# esquematico.net
KiCad netlist of a schematic drawn in Altium Designer
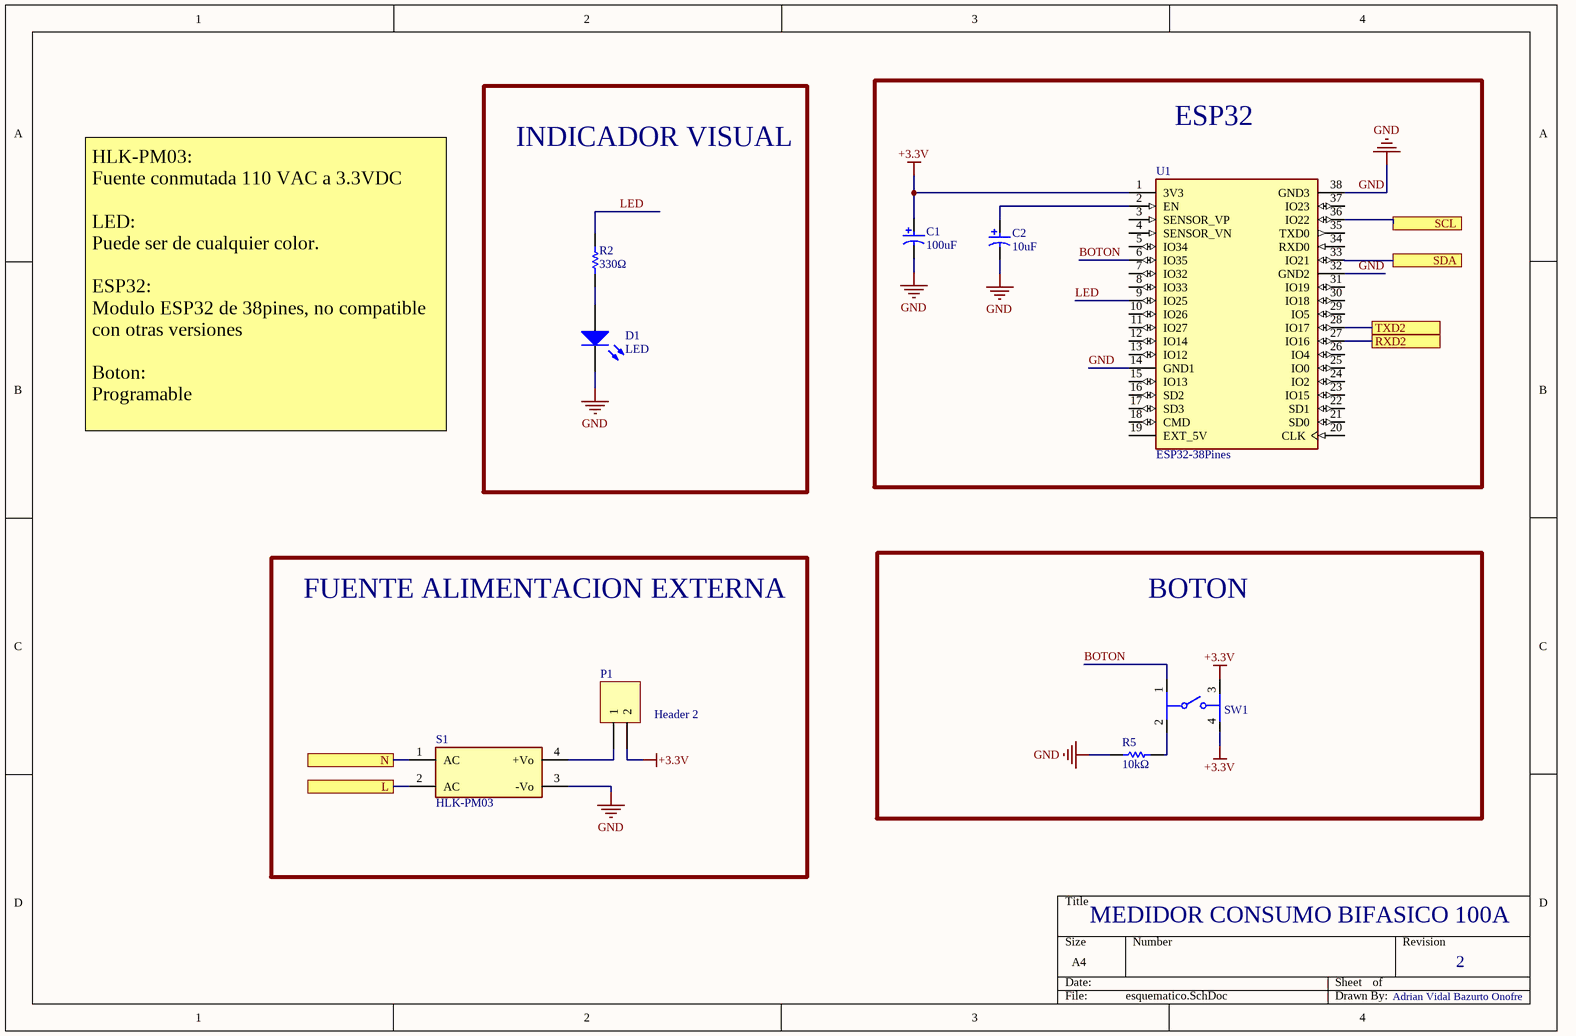
[diagram p0: esquematico.SchDoc]

(export (version "E")
  (design (tool "Eeschema 10.0.6"))
  (components
    (comp (ref "C1")
      (value "100uF")
      (footprint "FP-CAPACITOR")
      (libsource (lib "Simbologia") (part "Electrolytic capacitor"))
    )
    (comp (ref "C2")
      (value "10uF")
      (footprint "FP-CAPACITOR")
      (libsource (lib "Simbologia") (part "Electrolytic capacitor"))
    )
    (comp (ref "D1") (value "LED") (footprint "FP-LED") (libsource (lib "Simbologia") (part "LED")))
    (comp (ref "P1")
      (value "Header 2")
      (footprint "HDR1X2")
      (description "Header, 2-Pin")
      (fields (field (name "PUBLISHER") "Altium Limited"))
      (libsource (lib "Miscellaneous Connectors") (part "Header 2"))
    )
    (comp (ref "R2")
      (value "330Ω")
      (footprint "FP-RESISTENCIA")
      (libsource (lib "Simbologia") (part "Resistencia"))
    )
    (comp (ref "R5")
      (value "10kΩ")
      (footprint "FP-RESISTENCIA")
      (libsource (lib "Simbologia") (part "Resistencia"))
    )
    (comp (ref "S1")
      (value "HLK-PM03")
      (footprint "FP-HLK-PW12")
      (description "100-240V a 3.3V")
      (libsource (lib "Simbologia") (part "HLK-PM03"))
    )
    (comp (ref "SW1")
      (value "Button")
      (footprint "FP-BUTTON")
      (description "Button PCB")
      (libsource (lib "Simbologia") (part "Button"))
    )
    (comp (ref "U1")
      (value "ESP32-38Pines")
      (footprint "ESP32-38pin")
      (libsource (lib "user_ESP") (part "ESP32-38Pines"))
    )
  )
  (nets
    (net (code "1") (name "+3.3V") (class "Default")
      (node (ref "C1") (pin "1") (pinfunction "1_1") (pintype "passive"))
      (node (ref "P1") (pin "2") (pinfunction "2_2") (pintype "passive"))
      (node (ref "SW1") (pin "3") (pinfunction "3_3") (pintype "passive"))
      (node (ref "SW1") (pin "4") (pinfunction "4_4") (pintype "passive"))
      (node (ref "U1") (pin "1") (pinfunction "3V3_1") (pintype "power_in"))
    )
    (net (code "2") (name "/BOTON") (class "Default")
      (node (ref "SW1") (pin "1") (pinfunction "1_1") (pintype "passive"))
      (node (ref "U1") (pin "6") (pinfunction "IO35_6") (pintype "bidirectional"))
    )
    (net (code "3") (name "/L") (class "Default")
      (node (ref "S1") (pin "2") (pinfunction "AC_2") (pintype "power_in"))
    )
    (net (code "4") (name "/LED") (class "Default")
      (node (ref "R2") (pin "2") (pinfunction "2_2") (pintype "passive"))
      (node (ref "U1") (pin "9") (pinfunction "IO25_9") (pintype "bidirectional"))
    )
    (net (code "5") (name "/N") (class "Default")
      (node (ref "S1") (pin "1") (pinfunction "AC_1") (pintype "power_in"))
    )
    (net (code "6") (name "/RXD2") (class "Default")
      (node (ref "U1") (pin "27") (pinfunction "IO16_27") (pintype "bidirectional"))
    )
    (net (code "7") (name "/SCL") (class "Default")
      (node (ref "U1") (pin "36") (pinfunction "IO22_36") (pintype "bidirectional"))
    )
    (net (code "8") (name "/SDA") (class "Default")
      (node (ref "U1") (pin "33") (pinfunction "IO21_33") (pintype "bidirectional"))
    )
    (net (code "9") (name "/TXD2") (class "Default")
      (node (ref "U1") (pin "28") (pinfunction "IO17_28") (pintype "bidirectional"))
    )
    (net (code "10") (name "GND") (class "Default")
      (node (ref "C1") (pin "2") (pinfunction "2_2") (pintype "passive"))
      (node (ref "C2") (pin "2") (pinfunction "2_2") (pintype "passive"))
      (node (ref "D1") (pin "2") (pinfunction "K_2") (pintype "passive"))
      (node (ref "R5") (pin "1") (pinfunction "1_1") (pintype "passive"))
      (node (ref "S1") (pin "3") (pinfunction "-Vo_3") (pintype "power_in"))
      (node (ref "U1") (pin "14") (pinfunction "GND1_14") (pintype "power_in"))
      (node (ref "U1") (pin "32") (pinfunction "GND2_32") (pintype "power_in"))
      (node (ref "U1") (pin "38") (pinfunction "GND3_38") (pintype "power_in"))
    )
    (net (code "11") (name "Net-(D1-A)") (class "Default")
      (node (ref "D1") (pin "1") (pinfunction "A_1") (pintype "passive"))
      (node (ref "R2") (pin "1") (pinfunction "1_1") (pintype "passive"))
    )
    (net (code "12") (name "Net-(R5-Pad2)") (class "Default")
      (node (ref "R5") (pin "2") (pinfunction "2_2") (pintype "passive"))
      (node (ref "SW1") (pin "2") (pinfunction "2_2") (pintype "passive"))
    )
    (net (code "13") (name "Net-(S1-+Vo)") (class "Default")
      (node (ref "P1") (pin "1") (pinfunction "1_1") (pintype "passive"))
      (node (ref "S1") (pin "4") (pinfunction "+Vo_4") (pintype "power_in"))
    )
    (net (code "14") (name "Net-(U1-EN)") (class "Default")
      (node (ref "C2") (pin "1") (pinfunction "1_1") (pintype "passive"))
      (node (ref "U1") (pin "2") (pinfunction "EN_2") (pintype "input"))
    )
    (net (code "15") (name "unconnected-(U1-CLK-Pad20)") (class "Default")
      (node (ref "U1") (pin "20") (pinfunction "CLK_20") (pintype "input"))
    )
    (net (code "16") (name "unconnected-(U1-CMD-Pad18)") (class "Default")
      (node (ref "U1") (pin "18") (pinfunction "CMD_18") (pintype "bidirectional"))
    )
    (net (code "17") (name "unconnected-(U1-EXT_5V-Pad19)") (class "Default")
      (node (ref "U1") (pin "19") (pinfunction "EXT_5V_19") (pintype "power_in"))
    )
    (net (code "18") (name "unconnected-(U1-IO0-Pad25)") (class "Default")
      (node (ref "U1") (pin "25") (pinfunction "IO0_25") (pintype "bidirectional"))
    )
    (net (code "19") (name "unconnected-(U1-IO2-Pad24)") (class "Default")
      (node (ref "U1") (pin "24") (pinfunction "IO2_24") (pintype "bidirectional"))
    )
    (net (code "20") (name "unconnected-(U1-IO4-Pad26)") (class "Default")
      (node (ref "U1") (pin "26") (pinfunction "IO4_26") (pintype "bidirectional"))
    )
    (net (code "21") (name "unconnected-(U1-IO5-Pad29)") (class "Default")
      (node (ref "U1") (pin "29") (pinfunction "IO5_29") (pintype "bidirectional"))
    )
    (net (code "22") (name "unconnected-(U1-IO12-Pad13)") (class "Default")
      (node (ref "U1") (pin "13") (pinfunction "IO12_13") (pintype "bidirectional"))
    )
    (net (code "23") (name "unconnected-(U1-IO13-Pad15)") (class "Default")
      (node (ref "U1") (pin "15") (pinfunction "IO13_15") (pintype "bidirectional"))
    )
    (net (code "24") (name "unconnected-(U1-IO14-Pad12)") (class "Default")
      (node (ref "U1") (pin "12") (pinfunction "IO14_12") (pintype "bidirectional"))
    )
    (net (code "25") (name "unconnected-(U1-IO15-Pad23)") (class "Default")
      (node (ref "U1") (pin "23") (pinfunction "IO15_23") (pintype "bidirectional"))
    )
    (net (code "26") (name "unconnected-(U1-IO18-Pad30)") (class "Default")
      (node (ref "U1") (pin "30") (pinfunction "IO18_30") (pintype "bidirectional"))
    )
    (net (code "27") (name "unconnected-(U1-IO19-Pad31)") (class "Default")
      (node (ref "U1") (pin "31") (pinfunction "IO19_31") (pintype "bidirectional"))
    )
    (net (code "28") (name "unconnected-(U1-IO23-Pad37)") (class "Default")
      (node (ref "U1") (pin "37") (pinfunction "IO23_37") (pintype "bidirectional"))
    )
    (net (code "29") (name "unconnected-(U1-IO26-Pad10)") (class "Default")
      (node (ref "U1") (pin "10") (pinfunction "IO26_10") (pintype "bidirectional"))
    )
    (net (code "30") (name "unconnected-(U1-IO27-Pad11)") (class "Default")
      (node (ref "U1") (pin "11") (pinfunction "IO27_11") (pintype "bidirectional"))
    )
    (net (code "31") (name "unconnected-(U1-IO32-Pad7)") (class "Default")
      (node (ref "U1") (pin "7") (pinfunction "IO32_7") (pintype "bidirectional"))
    )
    (net (code "32") (name "unconnected-(U1-IO33-Pad8)") (class "Default")
      (node (ref "U1") (pin "8") (pinfunction "IO33_8") (pintype "bidirectional"))
    )
    (net (code "33") (name "unconnected-(U1-IO34-Pad5)") (class "Default")
      (node (ref "U1") (pin "5") (pinfunction "IO34_5") (pintype "bidirectional"))
    )
    (net (code "34") (name "unconnected-(U1-RXD0-Pad34)") (class "Default")
      (node (ref "U1") (pin "34") (pinfunction "RXD0_34") (pintype "input"))
    )
    (net (code "35") (name "unconnected-(U1-SD0-Pad21)") (class "Default")
      (node (ref "U1") (pin "21") (pinfunction "SD0_21") (pintype "bidirectional"))
    )
    (net (code "36") (name "unconnected-(U1-SD1-Pad22)") (class "Default")
      (node (ref "U1") (pin "22") (pinfunction "SD1_22") (pintype "bidirectional"))
    )
    (net (code "37") (name "unconnected-(U1-SD2-Pad16)") (class "Default")
      (node (ref "U1") (pin "16") (pinfunction "SD2_16") (pintype "bidirectional"))
    )
    (net (code "38") (name "unconnected-(U1-SD3-Pad17)") (class "Default")
      (node (ref "U1") (pin "17") (pinfunction "SD3_17") (pintype "bidirectional"))
    )
    (net (code "39") (name "unconnected-(U1-SENSOR_VN-Pad4)") (class "Default")
      (node (ref "U1") (pin "4") (pinfunction "SENSOR_VN_4") (pintype "input"))
    )
    (net (code "40") (name "unconnected-(U1-SENSOR_VP-Pad3)") (class "Default")
      (node (ref "U1") (pin "3") (pinfunction "SENSOR_VP_3") (pintype "input"))
    )
    (net (code "41") (name "unconnected-(U1-TXD0-Pad35)") (class "Default")
      (node (ref "U1") (pin "35") (pinfunction "TXD0_35") (pintype "output"))
    )
  )
)
